# Smart_Bird_Feeder.net
KiCad netlist of a schematic drawn in EAGLE
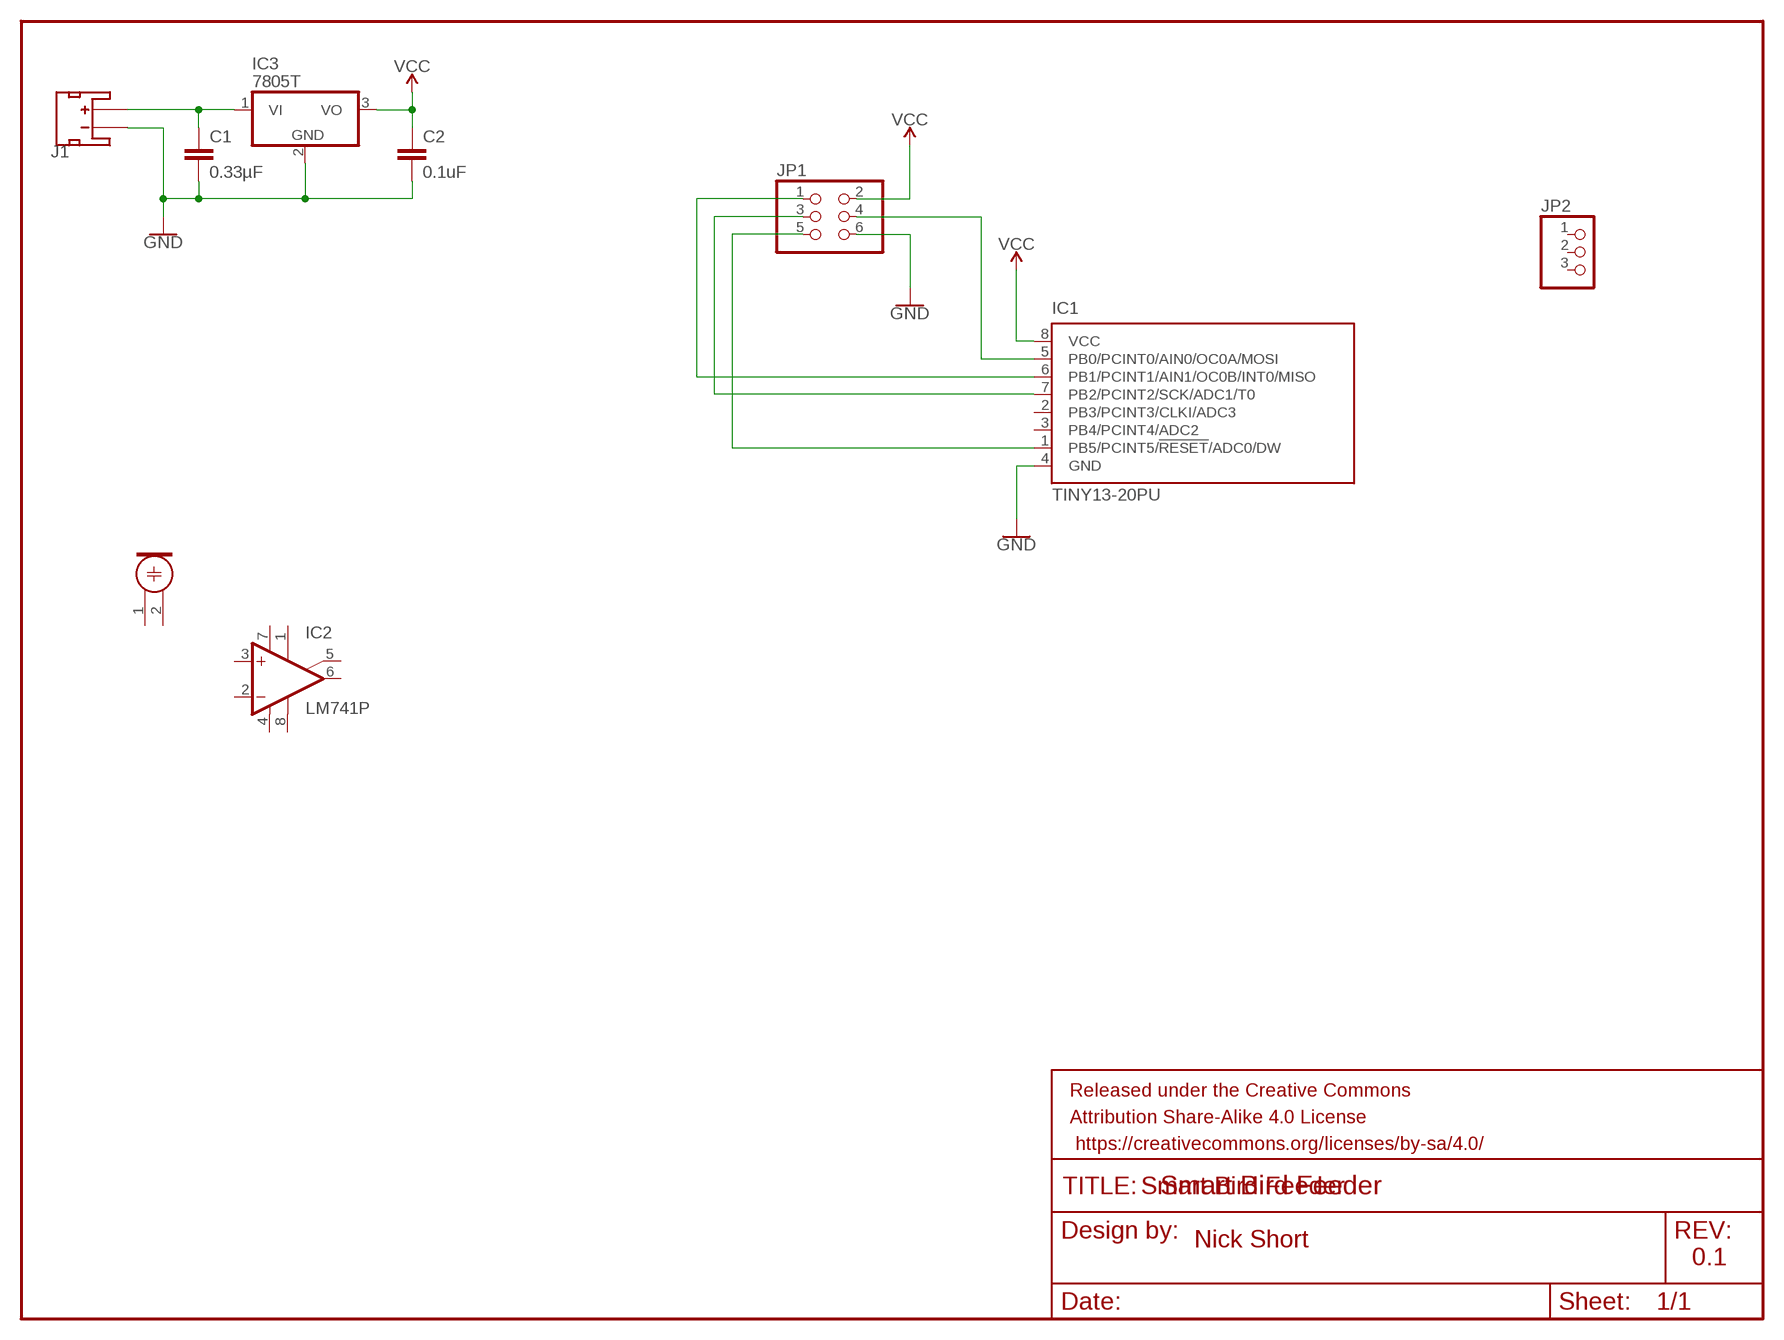
[diagram p0: schematic, sheet 1]

(export (version "E")
  (design (tool "Eeschema 10.0.6"))
  (components
    (comp (ref "C1")
      (value "0.33µF")
      (footprint "eagle-import:0805")
      (libsource (lib "eagle-import") (part "0.33UF/330NF-0805-50V-10%"))
    )
    (comp (ref "C2")
      (value "0.1uF")
      (footprint "eagle-import:0402")
      (libsource (lib "eagle-import") (part "0.1UF-0402-16V-10%"))
    )
    (comp (ref "FRAME1")
      (value "FRAME-LETTERNO_PACKAGE")
      (footprint "eagle-import:DUMMY")
      (fields (field (name "DESIGNER") "Nobody"))
      (libsource (lib "eagle-import") (part "FRAME-LETTERNO_PACKAGE"))
    )
    (comp (ref "IC1")
      (value "TINY13-20PU")
      (footprint "eagle-import:DIL08")
      (fields (field (name "MPN") "ATTINY13-20PU"))
      (libsource (lib "eagle-import") (part "TINY13PU-20"))
    )
    (comp (ref "IC2")
      (value "LM741P")
      (footprint "eagle-import:DIL08")
      (libsource (lib "eagle-import") (part "741PLM"))
    )
    (comp (ref "IC3")
      (value "7805T")
      (footprint "eagle-import:TO220H")
      (libsource (lib "eagle-import") (part "78T05"))
    )
    (comp (ref "J1")
      (value "JST_2MM_MALE")
      (footprint "eagle-import:JST-2-SMD")
      (libsource (lib "eagle-import") (part "JST_2MM_MALE"))
    )
    (comp (ref "JP1")
      (value "PINHD-2X3")
      (footprint "eagle-import:2X03")
      (libsource (lib "eagle-import") (part "PINHD-2X3"))
    )
    (comp (ref "JP2")
      (value "PINHD-1X3/90")
      (footprint "eagle-import:1X03_90")
      (libsource (lib "eagle-import") (part "PINHD-1X3/90"))
    )
    (comp (ref "M1")
      (value "ELECTRET_MICROPHON-WM-61A")
      (footprint "eagle-import:WM-61A")
      (libsource (lib "eagle-import") (part "ELECTRET_MICROPHON-WM-61A"))
    )
  )
  (nets
    (net (code "1") (name "/V+") (class "Default")
      (node (ref "IC2") (pin "7") (pinfunction "V+_7") (pintype "power_in"))
    )
    (net (code "2") (name "/V-") (class "Default")
      (node (ref "IC2") (pin "4") (pinfunction "V-_4") (pintype "power_in"))
    )
    (net (code "3") (name "GND") (class "Default")
      (node (ref "C1") (pin "2") (pinfunction "2_2") (pintype "passive"))
      (node (ref "C2") (pin "2") (pinfunction "2_2") (pintype "passive"))
      (node (ref "IC1") (pin "4") (pinfunction "GND_4") (pintype "power_in"))
      (node (ref "IC3") (pin "2") (pinfunction "GND_2") (pintype "passive"))
      (node (ref "J1") (pin "1") (pinfunction "-_1") (pintype "bidirectional"))
      (node (ref "JP1") (pin "6") (pinfunction "6_6") (pintype "passive"))
    )
    (net (code "4") (name "Net-(IC1-PB0{slash}PCINT0{slash}AIN0{slash}OC0A{slash}MOSI)") (class "Default")
      (node (ref "IC1") (pin "5") (pinfunction "PB0/PCINT0/AIN0/OC0A/MOSI_5") (pintype "bidirectional"))
      (node (ref "JP1") (pin "4") (pinfunction "4_4") (pintype "passive"))
    )
    (net (code "5") (name "Net-(IC1-PB1{slash}PCINT1{slash}AIN1{slash}OC0B{slash}INT0{slash}MISO)") (class "Default")
      (node (ref "IC1") (pin "6") (pinfunction "PB1/PCINT1/AIN1/OC0B/INT0/MISO_6") (pintype "bidirectional"))
      (node (ref "JP1") (pin "1") (pinfunction "1_1") (pintype "passive"))
    )
    (net (code "6") (name "Net-(IC1-PB2{slash}PCINT2{slash}SCK{slash}ADC1{slash}T0)") (class "Default")
      (node (ref "IC1") (pin "7") (pinfunction "PB2/PCINT2/SCK/ADC1/T0_7") (pintype "bidirectional"))
      (node (ref "JP1") (pin "3") (pinfunction "3_3") (pintype "passive"))
    )
    (net (code "7") (name "Net-(IC1-PB5{slash}PCINT5{slash}~{RESET}{slash}ADC0{slash}DW)") (class "Default")
      (node (ref "IC1") (pin "1") (pinfunction "PB5/PCINT5/~{RESET}/ADC0/DW_1") (pintype "bidirectional"))
      (node (ref "JP1") (pin "5") (pinfunction "5_5") (pintype "passive"))
    )
    (net (code "8") (name "Net-(IC3-VI)") (class "Default")
      (node (ref "C1") (pin "1") (pinfunction "1_1") (pintype "passive"))
      (node (ref "IC3") (pin "1") (pinfunction "VI_1") (pintype "input"))
      (node (ref "J1") (pin "2") (pinfunction "+_2") (pintype "bidirectional"))
    )
    (net (code "9") (name "VCC") (class "Default")
      (node (ref "C2") (pin "1") (pinfunction "1_1") (pintype "passive"))
      (node (ref "IC1") (pin "8") (pinfunction "VCC_8") (pintype "power_in"))
      (node (ref "IC3") (pin "3") (pinfunction "VO_3") (pintype "passive"))
      (node (ref "JP1") (pin "2") (pinfunction "2_2") (pintype "passive"))
    )
    (net (code "10") (name "unconnected-(IC1-PB3{slash}PCINT3{slash}CLKI{slash}ADC3-Pad2)") (class "Default")
      (node (ref "IC1") (pin "2") (pinfunction "PB3/PCINT3/CLKI/ADC3_2") (pintype "bidirectional"))
    )
    (net (code "11") (name "unconnected-(IC1-PB4{slash}PCINT4{slash}ADC2-Pad3)") (class "Default")
      (node (ref "IC1") (pin "3") (pinfunction "PB4/PCINT4/ADC2_3") (pintype "bidirectional"))
    )
    (net (code "12") (name "unconnected-(IC2-+IN-Pad3)") (class "Default")
      (node (ref "IC2") (pin "3") (pinfunction "+IN_3") (pintype "input"))
    )
    (net (code "13") (name "unconnected-(IC2--IN-Pad2)") (class "Default")
      (node (ref "IC2") (pin "2") (pinfunction "-IN_2") (pintype "input"))
    )
    (net (code "14") (name "unconnected-(IC2-ON1-Pad1)") (class "Default")
      (node (ref "IC2") (pin "1") (pinfunction "ON1_1") (pintype "passive"))
    )
    (net (code "15") (name "unconnected-(IC2-ON2-Pad5)") (class "Default")
      (node (ref "IC2") (pin "5") (pinfunction "ON2_5") (pintype "passive"))
    )
    (net (code "16") (name "unconnected-(IC2-OPT-Pad8)") (class "Default")
      (node (ref "IC2") (pin "8") (pinfunction "OPT_8") (pintype "passive"))
    )
    (net (code "17") (name "unconnected-(IC2-OUT-Pad6)") (class "Default")
      (node (ref "IC2") (pin "6") (pinfunction "OUT_6") (pintype "output"))
    )
    (net (code "18") (name "unconnected-(J1-PAD1-PadNC1)") (class "Default")
      (node (ref "J1") (pin "NC1") (pinfunction "PAD1_NC1") (pintype "bidirectional"))
    )
    (net (code "19") (name "unconnected-(J1-PAD2-PadNC2)") (class "Default")
      (node (ref "J1") (pin "NC2") (pinfunction "PAD2_NC2") (pintype "bidirectional"))
    )
    (net (code "20") (name "unconnected-(JP2-Pad1)") (class "Default")
      (node (ref "JP2") (pin "1") (pinfunction "1_1") (pintype "passive"))
    )
    (net (code "21") (name "unconnected-(JP2-Pad2)") (class "Default")
      (node (ref "JP2") (pin "2") (pinfunction "2_2") (pintype "passive"))
    )
    (net (code "22") (name "unconnected-(JP2-Pad3)") (class "Default")
      (node (ref "JP2") (pin "3") (pinfunction "3_3") (pintype "passive"))
    )
    (net (code "23") (name "unconnected-(M1-Pad1)") (class "Default")
      (node (ref "M1") (pin "1") (pinfunction "1_1") (pintype "passive"))
    )
    (net (code "24") (name "unconnected-(M1-Pad2)") (class "Default")
      (node (ref "M1") (pin "2") (pinfunction "2_2") (pintype "passive"))
    )
  )
)
